# TopLevel.net
KiCad netlist of a schematic drawn in Altium Designer
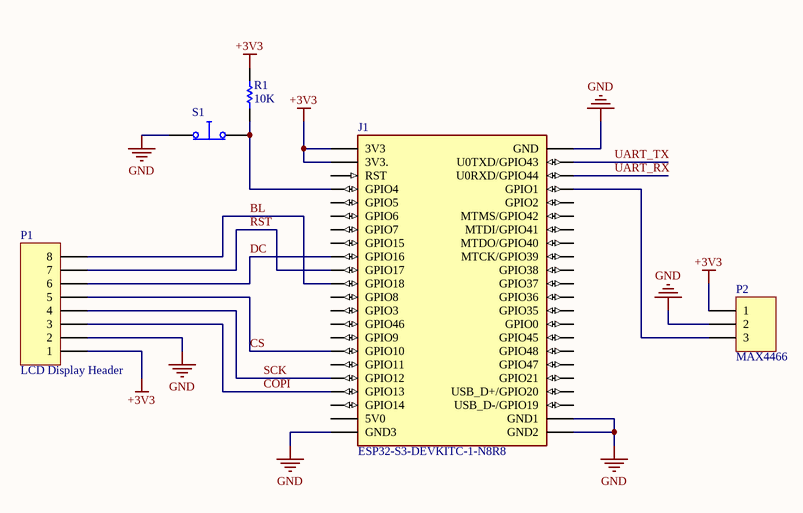
[diagram p0: TopLevel.SchDoc]

(export (version "E")
  (design (tool "Eeschema 10.0.6"))
  (components
    (comp (ref "J1")
      (value "ESP32-S3-DEVKITC-1-N8R8")
      (footprint "ESP32-S3-DEVKITC-1-N8R8")
      (fields (field (name "MF") "Espressif Systems"))
      (libsource (lib "Personal") (part "ESP32-S3-DEVKITC-1-N8R8"))
    )
    (comp (ref "P1")
      (value "LCD Display Header")
      (footprint "HDR1X8")
      (description "Header, 8-Pin")
      (fields (field (name "PUBLISHER") "Altium Limited"))
      (libsource (lib "Personal") (part "Header 8H"))
    )
    (comp (ref "P2")
      (value "MAX4466")
      (footprint "HDR1X3")
      (description "Header, 3-Pin")
      (fields (field (name "PUBLISHER") "Altium Limited"))
      (libsource (lib "Personal") (part "Header 3H"))
    )
    (comp (ref "R1")
      (value "10K")
      (description "Resistor")
      (libsource (lib "Simulation Generic Components") (part "Resistor"))
    )
    (comp (ref "S1")
      (value "Push Button Normally Closed")
      (libsource (lib "Simulation Generic Components") (part "Push Button NC"))
    )
  )
  (nets
    (net (code "1") (name "+3V3") (class "Default")
      (node (ref "J1") (pin "J1_1") (pinfunction "3V3_J1_1") (pintype "power_in"))
      (node (ref "J1") (pin "J1_2") (pinfunction "3V3._J1_2") (pintype "power_in"))
      (node (ref "P1") (pin "1") (pinfunction "1_1") (pintype "passive"))
      (node (ref "P2") (pin "1") (pinfunction "1_1") (pintype "passive"))
      (node (ref "R1") (pin "2") (pinfunction "2_2") (pintype "passive"))
    )
    (net (code "2") (name "/BL") (class "Default")
      (node (ref "J1") (pin "J1_11") (pinfunction "GPIO18_J1_11") (pintype "bidirectional"))
      (node (ref "P1") (pin "8") (pinfunction "8_8") (pintype "passive"))
    )
    (net (code "3") (name "/COPI") (class "Default")
      (node (ref "J1") (pin "J1_19") (pinfunction "GPIO13_J1_19") (pintype "bidirectional"))
      (node (ref "P1") (pin "3") (pinfunction "3_3") (pintype "passive"))
    )
    (net (code "4") (name "/CS") (class "Default")
      (node (ref "J1") (pin "J1_16") (pinfunction "GPIO10_J1_16") (pintype "bidirectional"))
      (node (ref "P1") (pin "5") (pinfunction "5_5") (pintype "passive"))
    )
    (net (code "5") (name "/DC") (class "Default")
      (node (ref "J1") (pin "J1_9") (pinfunction "GPIO16_J1_9") (pintype "bidirectional"))
      (node (ref "P1") (pin "6") (pinfunction "6_6") (pintype "passive"))
    )
    (net (code "6") (name "/RST") (class "Default")
      (node (ref "J1") (pin "J1_10") (pinfunction "GPIO17_J1_10") (pintype "bidirectional"))
      (node (ref "P1") (pin "7") (pinfunction "7_7") (pintype "passive"))
    )
    (net (code "7") (name "/SCK") (class "Default")
      (node (ref "J1") (pin "J1_18") (pinfunction "GPIO12_J1_18") (pintype "bidirectional"))
      (node (ref "P1") (pin "4") (pinfunction "4_4") (pintype "passive"))
    )
    (net (code "8") (name "/UART_RX") (class "Default")
      (node (ref "J1") (pin "J3_3") (pinfunction "U0RXD/GPIO44_J3_3") (pintype "bidirectional"))
    )
    (net (code "9") (name "/UART_TX") (class "Default")
      (node (ref "J1") (pin "J3_2") (pinfunction "U0TXD/GPIO43_J3_2") (pintype "bidirectional"))
    )
    (net (code "10") (name "GND") (class "Default")
      (node (ref "J1") (pin "J1_22") (pinfunction "GND3_J1_22") (pintype "power_in"))
      (node (ref "J1") (pin "J3_1") (pinfunction "GND_J3_1") (pintype "power_in"))
      (node (ref "J1") (pin "J3_21") (pinfunction "GND1_J3_21") (pintype "power_in"))
      (node (ref "J1") (pin "J3_22") (pinfunction "GND2_J3_22") (pintype "power_in"))
      (node (ref "P1") (pin "2") (pinfunction "2_2") (pintype "passive"))
      (node (ref "P2") (pin "2") (pinfunction "2_2") (pintype "passive"))
      (node (ref "S1") (pin "1") (pinfunction "1_1") (pintype "passive"))
    )
    (net (code "11") (name "Net-(J1-GPIO1)") (class "Default")
      (node (ref "J1") (pin "J3_4") (pinfunction "GPIO1_J3_4") (pintype "bidirectional"))
      (node (ref "P2") (pin "3") (pinfunction "3_3") (pintype "passive"))
    )
    (net (code "12") (name "Net-(J1-GPIO4)") (class "Default")
      (node (ref "J1") (pin "J1_4") (pinfunction "GPIO4_J1_4") (pintype "bidirectional"))
      (node (ref "R1") (pin "1") (pinfunction "1_1") (pintype "passive"))
      (node (ref "S1") (pin "2") (pinfunction "2_2") (pintype "passive"))
    )
    (net (code "13") (name "unconnected-(J1-5V0-PadJ1_21)") (class "Default")
      (node (ref "J1") (pin "J1_21") (pinfunction "5V0_J1_21") (pintype "power_in"))
    )
    (net (code "14") (name "unconnected-(J1-GPIO0-PadJ3_14)") (class "Default")
      (node (ref "J1") (pin "J3_14") (pinfunction "GPIO0_J3_14") (pintype "bidirectional"))
    )
    (net (code "15") (name "unconnected-(J1-GPIO2-PadJ3_5)") (class "Default")
      (node (ref "J1") (pin "J3_5") (pinfunction "GPIO2_J3_5") (pintype "bidirectional"))
    )
    (net (code "16") (name "unconnected-(J1-GPIO3-PadJ1_13)") (class "Default")
      (node (ref "J1") (pin "J1_13") (pinfunction "GPIO3_J1_13") (pintype "bidirectional"))
    )
    (net (code "17") (name "unconnected-(J1-GPIO5-PadJ1_5)") (class "Default")
      (node (ref "J1") (pin "J1_5") (pinfunction "GPIO5_J1_5") (pintype "bidirectional"))
    )
    (net (code "18") (name "unconnected-(J1-GPIO6-PadJ1_6)") (class "Default")
      (node (ref "J1") (pin "J1_6") (pinfunction "GPIO6_J1_6") (pintype "bidirectional"))
    )
    (net (code "19") (name "unconnected-(J1-GPIO7-PadJ1_7)") (class "Default")
      (node (ref "J1") (pin "J1_7") (pinfunction "GPIO7_J1_7") (pintype "bidirectional"))
    )
    (net (code "20") (name "unconnected-(J1-GPIO8-PadJ1_12)") (class "Default")
      (node (ref "J1") (pin "J1_12") (pinfunction "GPIO8_J1_12") (pintype "bidirectional"))
    )
    (net (code "21") (name "unconnected-(J1-GPIO9-PadJ1_15)") (class "Default")
      (node (ref "J1") (pin "J1_15") (pinfunction "GPIO9_J1_15") (pintype "bidirectional"))
    )
    (net (code "22") (name "unconnected-(J1-GPIO11-PadJ1_17)") (class "Default")
      (node (ref "J1") (pin "J1_17") (pinfunction "GPIO11_J1_17") (pintype "bidirectional"))
    )
    (net (code "23") (name "unconnected-(J1-GPIO14-PadJ1_20)") (class "Default")
      (node (ref "J1") (pin "J1_20") (pinfunction "GPIO14_J1_20") (pintype "bidirectional"))
    )
    (net (code "24") (name "unconnected-(J1-GPIO15-PadJ1_8)") (class "Default")
      (node (ref "J1") (pin "J1_8") (pinfunction "GPIO15_J1_8") (pintype "bidirectional"))
    )
    (net (code "25") (name "unconnected-(J1-GPIO21-PadJ3_18)") (class "Default")
      (node (ref "J1") (pin "J3_18") (pinfunction "GPIO21_J3_18") (pintype "bidirectional"))
    )
    (net (code "26") (name "unconnected-(J1-GPIO35-PadJ3_13)") (class "Default")
      (node (ref "J1") (pin "J3_13") (pinfunction "GPIO35_J3_13") (pintype "bidirectional"))
    )
    (net (code "27") (name "unconnected-(J1-GPIO36-PadJ3_12)") (class "Default")
      (node (ref "J1") (pin "J3_12") (pinfunction "GPIO36_J3_12") (pintype "bidirectional"))
    )
    (net (code "28") (name "unconnected-(J1-GPIO37-PadJ3_11)") (class "Default")
      (node (ref "J1") (pin "J3_11") (pinfunction "GPIO37_J3_11") (pintype "bidirectional"))
    )
    (net (code "29") (name "unconnected-(J1-GPIO38-PadJ3_10)") (class "Default")
      (node (ref "J1") (pin "J3_10") (pinfunction "GPIO38_J3_10") (pintype "bidirectional"))
    )
    (net (code "30") (name "unconnected-(J1-GPIO45-PadJ3_15)") (class "Default")
      (node (ref "J1") (pin "J3_15") (pinfunction "GPIO45_J3_15") (pintype "bidirectional"))
    )
    (net (code "31") (name "unconnected-(J1-GPIO46-PadJ1_14)") (class "Default")
      (node (ref "J1") (pin "J1_14") (pinfunction "GPIO46_J1_14") (pintype "bidirectional"))
    )
    (net (code "32") (name "unconnected-(J1-GPIO47-PadJ3_17)") (class "Default")
      (node (ref "J1") (pin "J3_17") (pinfunction "GPIO47_J3_17") (pintype "bidirectional"))
    )
    (net (code "33") (name "unconnected-(J1-GPIO48-PadJ3_16)") (class "Default")
      (node (ref "J1") (pin "J3_16") (pinfunction "GPIO48_J3_16") (pintype "bidirectional"))
    )
    (net (code "34") (name "unconnected-(J1-MTCK{slash}GPIO39-PadJ3_9)") (class "Default")
      (node (ref "J1") (pin "J3_9") (pinfunction "MTCK/GPIO39_J3_9") (pintype "bidirectional"))
    )
    (net (code "35") (name "unconnected-(J1-MTDI{slash}GPIO41-PadJ3_7)") (class "Default")
      (node (ref "J1") (pin "J3_7") (pinfunction "MTDI/GPIO41_J3_7") (pintype "bidirectional"))
    )
    (net (code "36") (name "unconnected-(J1-MTDO{slash}GPIO40-PadJ3_8)") (class "Default")
      (node (ref "J1") (pin "J3_8") (pinfunction "MTDO/GPIO40_J3_8") (pintype "bidirectional"))
    )
    (net (code "37") (name "unconnected-(J1-MTMS{slash}GPIO42-PadJ3_6)") (class "Default")
      (node (ref "J1") (pin "J3_6") (pinfunction "MTMS/GPIO42_J3_6") (pintype "bidirectional"))
    )
    (net (code "38") (name "unconnected-(J1-RST-PadJ1_3)") (class "Default")
      (node (ref "J1") (pin "J1_3") (pinfunction "RST_J1_3") (pintype "input"))
    )
    (net (code "39") (name "unconnected-(J1-USB_D+{slash}GPIO20-PadJ3_19)") (class "Default")
      (node (ref "J1") (pin "J3_19") (pinfunction "USB_D+/GPIO20_J3_19") (pintype "bidirectional"))
    )
    (net (code "40") (name "unconnected-(J1-USB_D-{slash}GPIO19-PadJ3_20)") (class "Default")
      (node (ref "J1") (pin "J3_20") (pinfunction "USB_D-/GPIO19_J3_20") (pintype "bidirectional"))
    )
  )
)
